# LPCB280_-_RM57_LAUNCH.net
KiCad netlist of a schematic drawn in Altium Designer
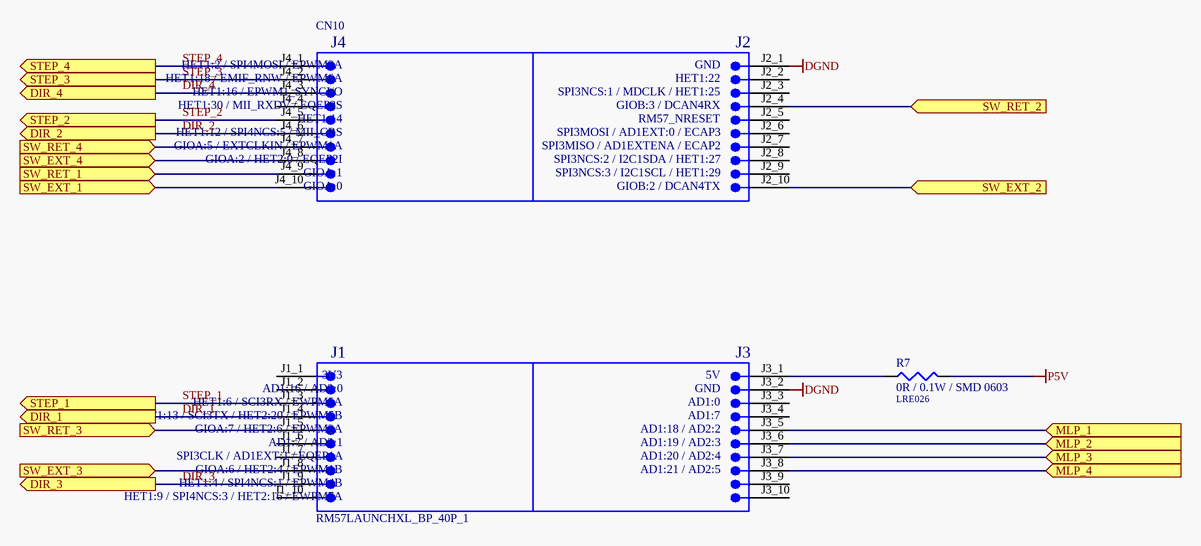
[diagram p0: LPCB280 - RM57 LAUNCH.SchDoc]

(export (version "E")
  (design (tool "Eeschema 10.0.6"))
  (components
    (comp (ref "CN10")
      (value "RM57LAUNCHXL_BP_40P_1")
      (footprint "RM57LAUNCHXL_BP_40P_1")
      (description "Connector, RM57L843 LaunchXL, 40Pin Boosterpack Site1")
      (libsource (lib "LDL_Connectors") (part "RM57LAUNCHXL_BP_40P_1"))
    )
    (comp (ref "R7")
      (value "0R / 0.1W / SMD 0603")
      (footprint "LFP020__CR1608-0603-IPC7351_B")
      (description "Resistor, Ceramic Chip, 0R, 0.1W, SMD 0603 [LRE026]")
      (fields (field (name "LDL_NUMBER") "LRE026"))
      (libsource (lib "LDL_Resistors") (part "0R / 0.1W / SMD 0603"))
    )
  )
  (nets
    (net (code "1") (name "/DIR_1") (class "Default") (node (ref "CN10") (pin "J1_4") (pintype "passive")))
    (net (code "2") (name "/DIR_2") (class "Default") (node (ref "CN10") (pin "J4_6") (pintype "passive")))
    (net (code "3") (name "/DIR_3") (class "Default") (node (ref "CN10") (pin "J1_9") (pintype "passive")))
    (net (code "4") (name "/DIR_4") (class "Default") (node (ref "CN10") (pin "J4_3") (pintype "passive")))
    (net (code "5") (name "/MLP_1") (class "Default") (node (ref "CN10") (pin "J3_5") (pintype "passive")))
    (net (code "6") (name "/MLP_2") (class "Default") (node (ref "CN10") (pin "J3_6") (pintype "passive")))
    (net (code "7") (name "/MLP_3") (class "Default") (node (ref "CN10") (pin "J3_7") (pintype "passive")))
    (net (code "8") (name "/MLP_4") (class "Default") (node (ref "CN10") (pin "J3_8") (pintype "passive")))
    (net (code "9") (name "/STEP_1") (class "Default") (node (ref "CN10") (pin "J1_3") (pintype "passive")))
    (net (code "10") (name "/STEP_2") (class "Default") (node (ref "CN10") (pin "J4_5") (pintype "passive")))
    (net (code "11") (name "/STEP_3") (class "Default") (node (ref "CN10") (pin "J4_2") (pintype "passive")))
    (net (code "12") (name "/STEP_4") (class "Default") (node (ref "CN10") (pin "J4_1") (pintype "passive")))
    (net (code "13") (name "/SW_EXT_1") (class "Default")
      (node (ref "CN10") (pin "J4_10") (pintype "passive"))
    )
    (net (code "14") (name "/SW_EXT_2") (class "Default")
      (node (ref "CN10") (pin "J2_10") (pintype "passive"))
    )
    (net (code "15") (name "/SW_EXT_3") (class "Default")
      (node (ref "CN10") (pin "J1_8") (pintype "passive"))
    )
    (net (code "16") (name "/SW_EXT_4") (class "Default")
      (node (ref "CN10") (pin "J4_8") (pintype "passive"))
    )
    (net (code "17") (name "/SW_RET_1") (class "Default")
      (node (ref "CN10") (pin "J4_9") (pintype "passive"))
    )
    (net (code "18") (name "/SW_RET_2") (class "Default")
      (node (ref "CN10") (pin "J2_4") (pintype "passive"))
    )
    (net (code "19") (name "/SW_RET_3") (class "Default")
      (node (ref "CN10") (pin "J1_5") (pintype "passive"))
    )
    (net (code "20") (name "/SW_RET_4") (class "Default")
      (node (ref "CN10") (pin "J4_7") (pintype "passive"))
    )
    (net (code "21") (name "DGND") (class "Default")
      (node (ref "CN10") (pin "J2_1") (pintype "passive"))
      (node (ref "CN10") (pin "J3_2") (pintype "passive"))
    )
    (net (code "22") (name "Net-(CN10-PadJ3_1)") (class "Default")
      (node (ref "CN10") (pin "J3_1") (pintype "passive"))
      (node (ref "R7") (pin "1") (pintype "passive"))
    )
    (net (code "23") (name "P5V") (class "Default") (node (ref "R7") (pin "2") (pintype "passive")))
    (net (code "24") (name "unconnected-(CN10-PadJ1_1)") (class "Default")
      (node (ref "CN10") (pin "J1_1") (pintype "passive"))
    )
    (net (code "25") (name "unconnected-(CN10-PadJ1_2)") (class "Default")
      (node (ref "CN10") (pin "J1_2") (pintype "passive"))
    )
    (net (code "26") (name "unconnected-(CN10-PadJ1_6)") (class "Default")
      (node (ref "CN10") (pin "J1_6") (pintype "passive"))
    )
    (net (code "27") (name "unconnected-(CN10-PadJ1_7)") (class "Default")
      (node (ref "CN10") (pin "J1_7") (pintype "passive"))
    )
    (net (code "28") (name "unconnected-(CN10-PadJ1_10)") (class "Default")
      (node (ref "CN10") (pin "J1_10") (pintype "passive"))
    )
    (net (code "29") (name "unconnected-(CN10-PadJ2_2)") (class "Default")
      (node (ref "CN10") (pin "J2_2") (pintype "passive"))
    )
    (net (code "30") (name "unconnected-(CN10-PadJ2_3)") (class "Default")
      (node (ref "CN10") (pin "J2_3") (pintype "passive"))
    )
    (net (code "31") (name "unconnected-(CN10-PadJ2_5)") (class "Default")
      (node (ref "CN10") (pin "J2_5") (pintype "passive"))
    )
    (net (code "32") (name "unconnected-(CN10-PadJ2_6)") (class "Default")
      (node (ref "CN10") (pin "J2_6") (pintype "passive"))
    )
    (net (code "33") (name "unconnected-(CN10-PadJ2_7)") (class "Default")
      (node (ref "CN10") (pin "J2_7") (pintype "passive"))
    )
    (net (code "34") (name "unconnected-(CN10-PadJ2_8)") (class "Default")
      (node (ref "CN10") (pin "J2_8") (pintype "passive"))
    )
    (net (code "35") (name "unconnected-(CN10-PadJ2_9)") (class "Default")
      (node (ref "CN10") (pin "J2_9") (pintype "passive"))
    )
    (net (code "36") (name "unconnected-(CN10-PadJ3_3)") (class "Default")
      (node (ref "CN10") (pin "J3_3") (pintype "passive"))
    )
    (net (code "37") (name "unconnected-(CN10-PadJ3_4)") (class "Default")
      (node (ref "CN10") (pin "J3_4") (pintype "passive"))
    )
    (net (code "38") (name "unconnected-(CN10-PadJ3_9)") (class "Default")
      (node (ref "CN10") (pin "J3_9") (pintype "passive"))
    )
    (net (code "39") (name "unconnected-(CN10-PadJ3_10)") (class "Default")
      (node (ref "CN10") (pin "J3_10") (pintype "passive"))
    )
    (net (code "40") (name "unconnected-(CN10-PadJ4_4)") (class "Default")
      (node (ref "CN10") (pin "J4_4") (pintype "passive"))
    )
  )
)
